# MCU.net
KiCad netlist of a schematic drawn in Altium Designer
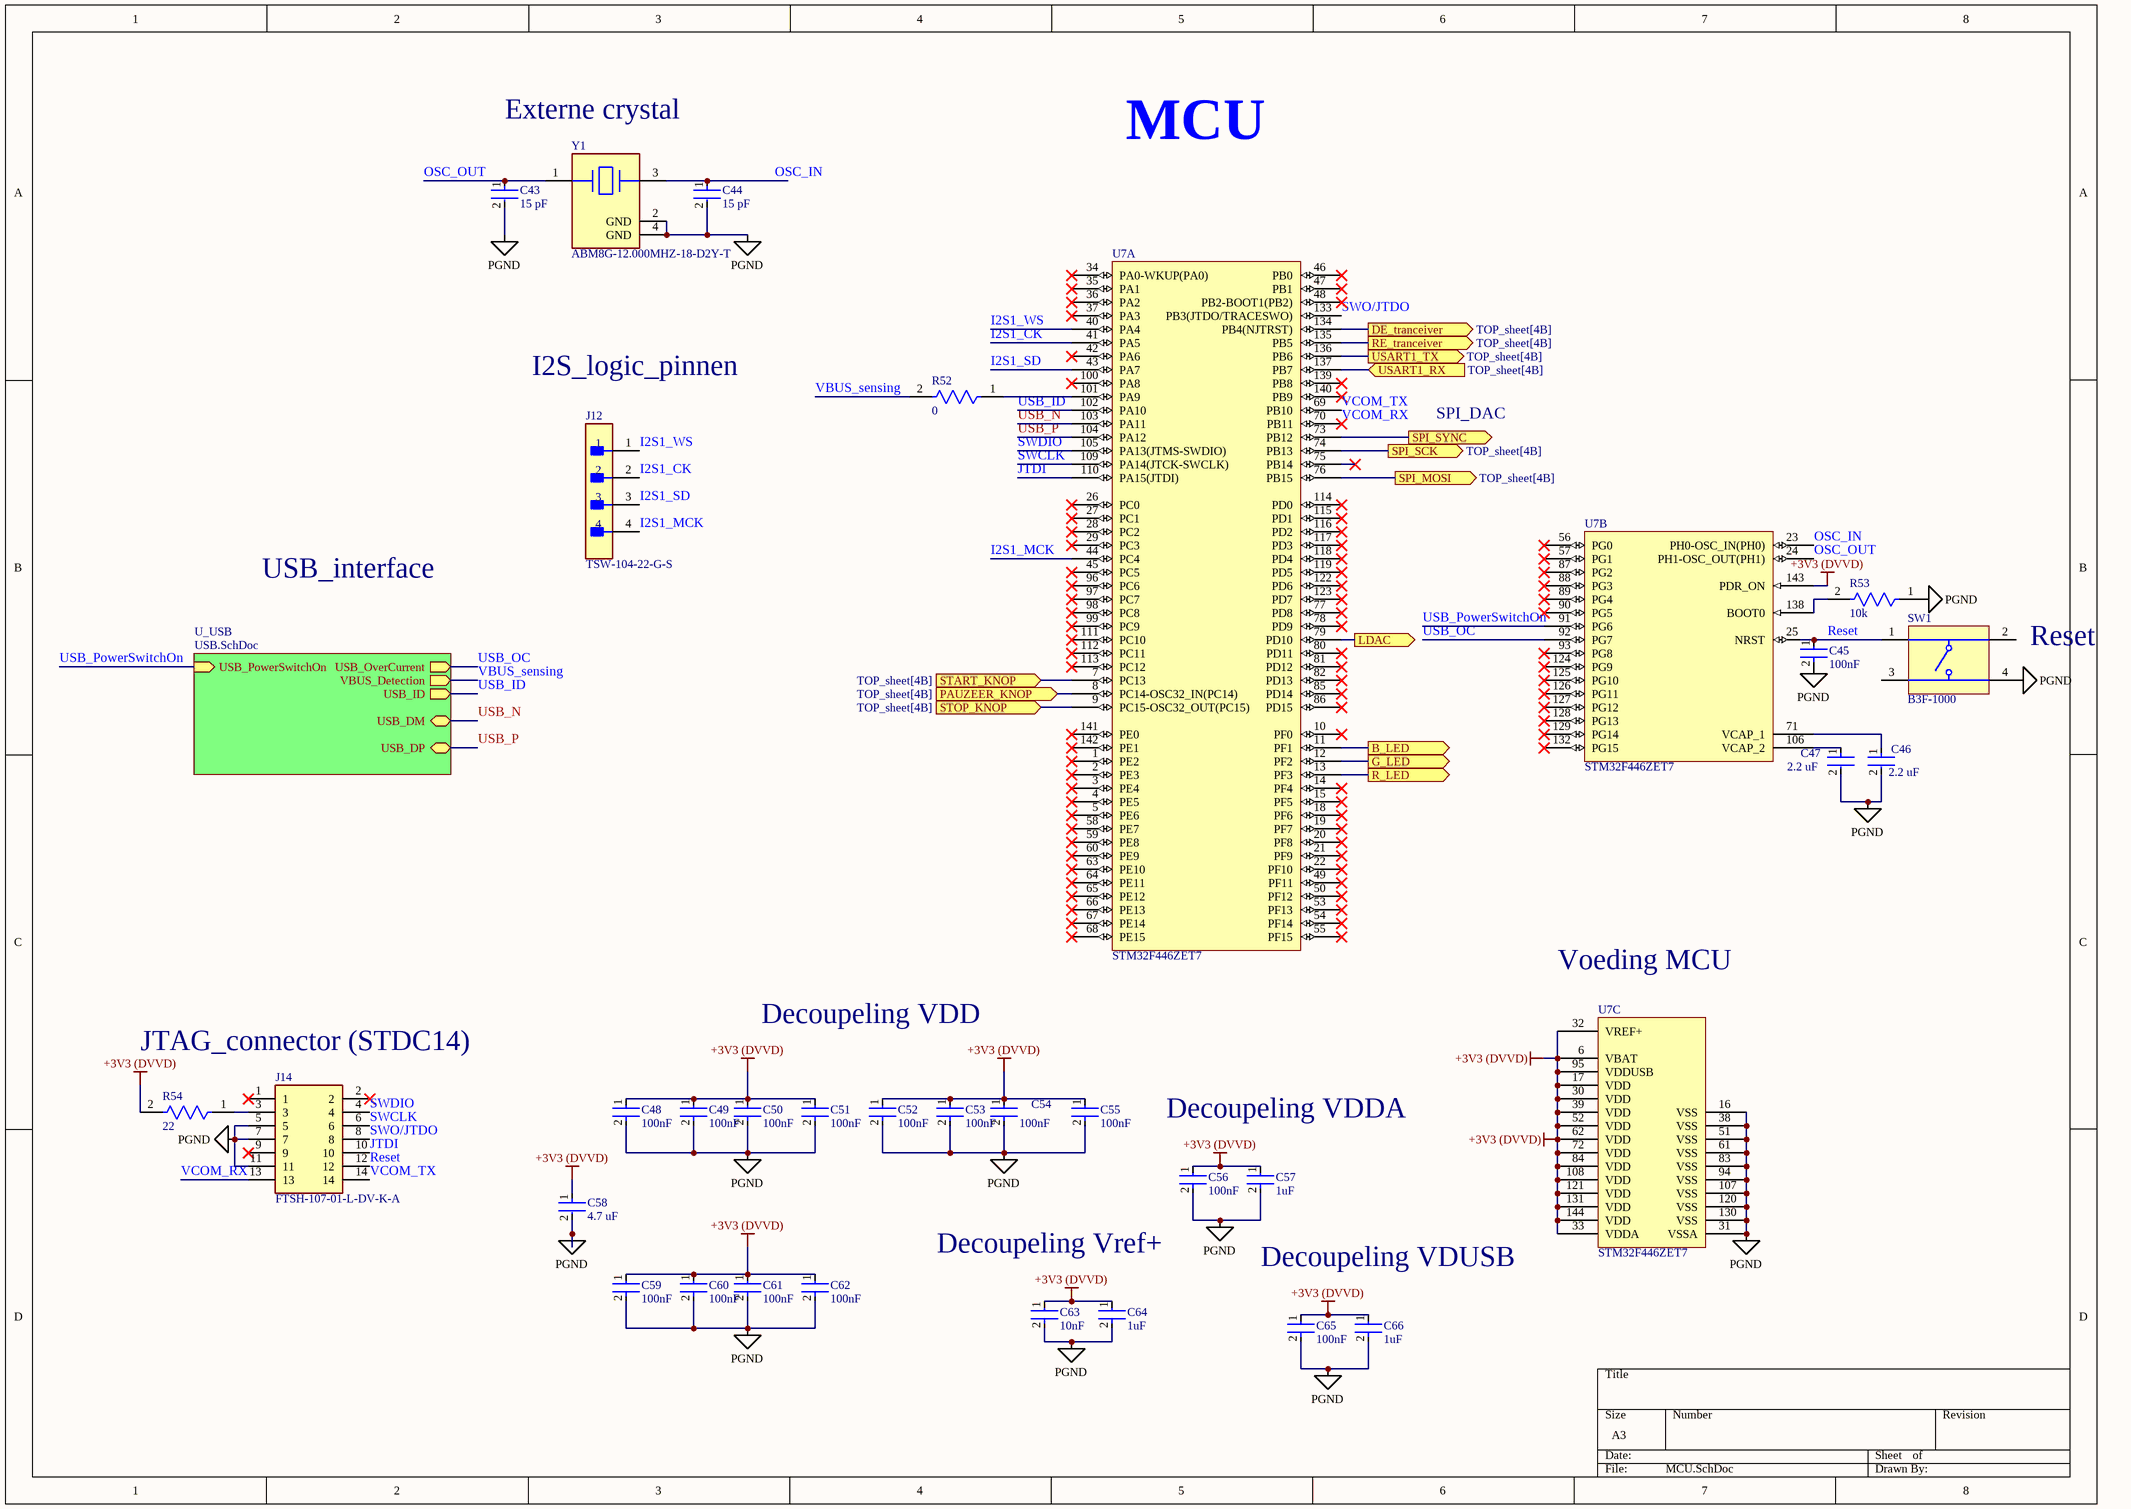
[diagram p0: MCU.SchDoc]

(export (version "E")
  (design (tool "Eeschema 10.0.6"))
  (components
    (comp (ref "C43")
      (value "15 pF")
      (footprint "FP-AC0603-MFG")
      (description "AC0603 15 pF NP0 5.00% 50 V")
      (fields
        (field (name "TOLERANCE") "0.05")
        (field (name "OCTOPART") "https://octopart.com/ac0603jrnpo9bn271-yageo-87214073")
      )
      (libsource (lib "Altium Content Vault") (part "11868f565c42a9108669ba33697ecf6"))
    )
    (comp (ref "C44")
      (value "15 pF")
      (footprint "FP-AC0603-MFG")
      (description "AC0603 15 pF NP0 5.00% 50 V")
      (fields
        (field (name "TOLERANCE") "0.05")
        (field (name "OCTOPART") "https://octopart.com/ac0603jrnpo9bn271-yageo-87214073")
      )
      (libsource (lib "Altium Content Vault") (part "11868f565c42a9108669ba33697ecf6"))
    )
    (comp (ref "C45")
      (value "100nF")
      (footprint "FP-GRM15-MFG")
      (description "CAP CER 0.1UF 16V X7R 0402")
      (fields (field (name "MANUFACTURER PART NUMBER") "GRM155R71C104KA88D") (field (name "TOLERANCE") "10%"))
      (libsource (lib "Altium Content Vault") (part "236180d848d6139a670b325ea6854c9"))
    )
    (comp (ref "C46")
      (value "2.2 uF")
      (footprint "FP-C0603C-CF-MFG")
      (description "CAP CER 2.2 UF 50V 5% X7R 0603")
      (fields (field (name "TOLERANCE") "0.05") (field (name "MANUFACTURER PART NUMBER") "C0603C104J5RACTU"))
      (libsource (lib "Altium Content Vault") (part "b4654b650e69147ec39a6b967a45e02"))
    )
    (comp (ref "C47")
      (value "2.2 uF")
      (footprint "FP-C0603C-CF-MFG")
      (description "CAP CER 2.2 UF 50V 5% X7R 0603")
      (fields (field (name "TOLERANCE") "0.05") (field (name "MANUFACTURER PART NUMBER") "C0603C104J5RACTU"))
      (libsource (lib "Altium Content Vault") (part "b4654b650e69147ec39a6b967a45e02"))
    )
    (comp (ref "C48")
      (value "100nF")
      (footprint "FP-GRM15-MFG")
      (description "CAP CER 0.1UF 16V X7R 0402")
      (fields (field (name "MANUFACTURER PART NUMBER") "GRM155R71C104KA88D") (field (name "TOLERANCE") "10%"))
      (libsource (lib "Altium Content Vault") (part "236180d848d6139a670b325ea6854c9"))
    )
    (comp (ref "C49")
      (value "100nF")
      (footprint "FP-GRM15-MFG")
      (description "CAP CER 0.1UF 16V X7R 0402")
      (fields (field (name "MANUFACTURER PART NUMBER") "GRM155R71C104KA88D") (field (name "TOLERANCE") "10%"))
      (libsource (lib "Altium Content Vault") (part "236180d848d6139a670b325ea6854c9"))
    )
    (comp (ref "C50")
      (value "100nF")
      (footprint "FP-GRM15-MFG")
      (description "CAP CER 0.1UF 16V X7R 0402")
      (fields (field (name "MANUFACTURER PART NUMBER") "GRM155R71C104KA88D") (field (name "TOLERANCE") "10%"))
      (libsource (lib "Altium Content Vault") (part "236180d848d6139a670b325ea6854c9"))
    )
    (comp (ref "C51")
      (value "100nF")
      (footprint "FP-GRM15-MFG")
      (description "CAP CER 0.1UF 16V X7R 0402")
      (fields (field (name "MANUFACTURER PART NUMBER") "GRM155R71C104KA88D") (field (name "TOLERANCE") "10%"))
      (libsource (lib "Altium Content Vault") (part "236180d848d6139a670b325ea6854c9"))
    )
    (comp (ref "C52")
      (value "100nF")
      (footprint "FP-GRM15-MFG")
      (description "CAP CER 0.1UF 16V X7R 0402")
      (fields (field (name "MANUFACTURER PART NUMBER") "GRM155R71C104KA88D") (field (name "TOLERANCE") "10%"))
      (libsource (lib "Altium Content Vault") (part "236180d848d6139a670b325ea6854c9"))
    )
    (comp (ref "C53")
      (value "100nF")
      (footprint "FP-GRM15-MFG")
      (description "CAP CER 0.1UF 16V X7R 0402")
      (fields (field (name "MANUFACTURER PART NUMBER") "GRM155R71C104KA88D") (field (name "TOLERANCE") "10%"))
      (libsource (lib "Altium Content Vault") (part "236180d848d6139a670b325ea6854c9"))
    )
    (comp (ref "C54")
      (value "100nF")
      (footprint "FP-GRM15-MFG")
      (description "CAP CER 0.1UF 16V X7R 0402")
      (fields (field (name "MANUFACTURER PART NUMBER") "GRM155R71C104KA88D") (field (name "TOLERANCE") "10%"))
      (libsource (lib "Altium Content Vault") (part "236180d848d6139a670b325ea6854c9"))
    )
    (comp (ref "C55")
      (value "100nF")
      (footprint "FP-GRM15-MFG")
      (description "CAP CER 0.1UF 16V X7R 0402")
      (fields (field (name "MANUFACTURER PART NUMBER") "GRM155R71C104KA88D") (field (name "TOLERANCE") "10%"))
      (libsource (lib "Altium Content Vault") (part "236180d848d6139a670b325ea6854c9"))
    )
    (comp (ref "C56")
      (value "100nF")
      (footprint "FP-GRM15-MFG")
      (description "CAP CER 0.1UF 16V X7R 0402")
      (fields (field (name "MANUFACTURER PART NUMBER") "GRM155R71C104KA88D") (field (name "TOLERANCE") "10%"))
      (libsource (lib "Altium Content Vault") (part "236180d848d6139a670b325ea6854c9"))
    )
    (comp (ref "C57")
      (value "1uF")
      (footprint "FP-GRM15-MFG")
      (description "CAP CER 1UF 16V X7R 0402")
      (fields (field (name "MANUFACTURER PART NUMBER") "GRM155R71C104KA88D") (field (name "TOLERANCE") "10%"))
      (libsource (lib "Altium Content Vault") (part "236180d848d6139a670b325ea6854c9"))
    )
    (comp (ref "C58")
      (value "4.7 uF")
      (footprint "FP-C0603C-CF-MFG")
      (description "CAP CER 4.7 UF 50V 5% X7R 0603")
      (fields (field (name "TOLERANCE") "0.05") (field (name "MANUFACTURER PART NUMBER") "C0603C104J5RACTU"))
      (libsource (lib "Altium Content Vault") (part "b4654b650e69147ec39a6b967a45e02"))
    )
    (comp (ref "C59")
      (value "100nF")
      (footprint "FP-GRM15-MFG")
      (description "CAP CER 0.1UF 16V X7R 0402")
      (fields (field (name "MANUFACTURER PART NUMBER") "GRM155R71C104KA88D") (field (name "TOLERANCE") "10%"))
      (libsource (lib "Altium Content Vault") (part "236180d848d6139a670b325ea6854c9"))
    )
    (comp (ref "C60")
      (value "100nF")
      (footprint "FP-GRM15-MFG")
      (description "CAP CER 0.1UF 16V X7R 0402")
      (fields (field (name "MANUFACTURER PART NUMBER") "GRM155R71C104KA88D") (field (name "TOLERANCE") "10%"))
      (libsource (lib "Altium Content Vault") (part "236180d848d6139a670b325ea6854c9"))
    )
    (comp (ref "C61")
      (value "100nF")
      (footprint "FP-GRM15-MFG")
      (description "CAP CER 0.1UF 16V X7R 0402")
      (fields (field (name "MANUFACTURER PART NUMBER") "GRM155R71C104KA88D") (field (name "TOLERANCE") "10%"))
      (libsource (lib "Altium Content Vault") (part "236180d848d6139a670b325ea6854c9"))
    )
    (comp (ref "C62")
      (value "100nF")
      (footprint "FP-GRM15-MFG")
      (description "CAP CER 0.1UF 16V X7R 0402")
      (fields (field (name "MANUFACTURER PART NUMBER") "GRM155R71C104KA88D") (field (name "TOLERANCE") "10%"))
      (libsource (lib "Altium Content Vault") (part "236180d848d6139a670b325ea6854c9"))
    )
    (comp (ref "C63")
      (value "10nF")
      (footprint "FP-GRM15-MFG")
      (description "CAP CER 10nF 16V X7R 0402")
      (fields (field (name "MANUFACTURER PART NUMBER") "GRM155R71C104KA88D") (field (name "TOLERANCE") "10%"))
      (libsource (lib "Altium Content Vault") (part "236180d848d6139a670b325ea6854c9"))
    )
    (comp (ref "C64")
      (value "1uF")
      (footprint "FP-GRM15-MFG")
      (description "CAP CER 1UF 16V X7R 0402")
      (fields (field (name "MANUFACTURER PART NUMBER") "GRM155R71C104KA88D") (field (name "TOLERANCE") "10%"))
      (libsource (lib "Altium Content Vault") (part "236180d848d6139a670b325ea6854c9"))
    )
    (comp (ref "C65")
      (value "100nF")
      (footprint "FP-GRM15-MFG")
      (description "CAP CER 0.1UF 16V X7R 0402")
      (fields (field (name "MANUFACTURER PART NUMBER") "GRM155R71C104KA88D") (field (name "TOLERANCE") "10%"))
      (libsource (lib "Altium Content Vault") (part "236180d848d6139a670b325ea6854c9"))
    )
    (comp (ref "C66")
      (value "1uF")
      (footprint "FP-GRM15-MFG")
      (description "CAP CER 1UF 16V X7R 0402")
      (fields (field (name "MANUFACTURER PART NUMBER") "GRM155R71C104KA88D") (field (name "TOLERANCE") "10%"))
      (libsource (lib "Altium Content Vault") (part "236180d848d6139a670b325ea6854c9"))
    )
    (comp (ref "J12")
      (value "TSW-104-22-G-S")
      (footprint "FP-TSW-104-22-G-S-MFG")
      (description "GENERIC PART NUMBER: GPHA-1X04\r\nCONN HEADER VERT 4POS 2.54MM")
      (fields (field (name "GENERIC PART NUMBER") "GPHA-1X04"))
      (libsource (lib "Altium Content Vault") (part "299a8cea1bdcbc3624fe62c390fa72c"))
    )
    (comp (ref "J14")
      (value "FTSH-107-01-L-DV-K-A")
      (footprint "SamacSys:FTSH-107-XX-YYY-DV-K-A")
      (fields (field (name "MOUSER PART NUMBER") "200-FTSH10701LDVKA"))
      (libsource (lib "*") (part "FTSH-107-01-L-DV-K-A"))
    )
    (comp (ref "R52")
      (value "0")
      (footprint "FP-CRCW1206-MFG")
      (description "CRCW12060000ZSTA Zero Ohm Resistor, Jumper, 1206 [3216 Metric], Thick Film, 250 mW, Surface Mount")
      (libsource (lib "Altium Content Vault") (part "1029c3af85768c4190bb7ad29bc67b5"))
    )
    (comp (ref "R53")
      (value "10k")
      (footprint "FP-RC1608-IPC_B")
      (fields (field (name "TOLERANCE") "1%"))
      (libsource (lib "Altium Content Vault") (part "1029c3af85768c4190bb7ad29bc67b5"))
    )
    (comp (ref "R54")
      (value "22")
      (footprint "FP-RC1608-IPC_B")
      (fields (field (name "TOLERANCE") "1%"))
      (libsource (lib "Altium Content Vault") (part "1029c3af85768c4190bb7ad29bc67b5"))
    )
    (comp (ref "SW1")
      (value "B3F-1000")
      (footprint "OMRON-B3F-1000-4_V")
      (description "Tactile Switch, SPST-NO, 0.05 A, 5 to 24 V, -25 to 70 degC, 4-Pin THD, RoHS, Bulk")
      (libsource (lib "Altium Content Vault") (part "SW-SPST-4_A"))
    )
    (comp (ref "U7")
      (value "STM32F446ZET7")
      (footprint "STM-LQFP144_M")
      (libsource (lib "Altium Content Vault") (part "MC-ARM-STM32F446-LQFP144"))
    )
    (comp (ref "Y1")
      (value "ABM8G-12.000MHZ-18-D2Y-T")
      (footprint "FP-ABM8G-MFG")
      (description "Crystal 12MHz ±20ppm (Tol) ±30ppm (Stability) 18pF FUND 120Ω 4-Pin SMD T/R")
      (fields (field (name "TOLERANCE") "20ppm"))
      (libsource (lib "Altium Content Vault") (part "48e526d86b7f2615d98721063c72f49"))
    )
  )
  (nets
    (net (code "1") (name "+3V3 (DVVD)") (class "Default")
      (node (ref "C48") (pin "1") (pinfunction "1_1") (pintype "passive"))
      (node (ref "C49") (pin "1") (pinfunction "1_1") (pintype "passive"))
      (node (ref "C50") (pin "1") (pinfunction "1_1") (pintype "passive"))
      (node (ref "C51") (pin "1") (pinfunction "1_1") (pintype "passive"))
      (node (ref "C52") (pin "1") (pinfunction "1_1") (pintype "passive"))
      (node (ref "C53") (pin "1") (pinfunction "1_1") (pintype "passive"))
      (node (ref "C54") (pin "1") (pinfunction "1_1") (pintype "passive"))
      (node (ref "C55") (pin "1") (pinfunction "1_1") (pintype "passive"))
      (node (ref "C56") (pin "1") (pinfunction "1_1") (pintype "passive"))
      (node (ref "C57") (pin "1") (pinfunction "1_1") (pintype "passive"))
      (node (ref "C58") (pin "1") (pinfunction "1_1") (pintype "passive"))
      (node (ref "C59") (pin "1") (pinfunction "1_1") (pintype "passive"))
      (node (ref "C60") (pin "1") (pinfunction "1_1") (pintype "passive"))
      (node (ref "C61") (pin "1") (pinfunction "1_1") (pintype "passive"))
      (node (ref "C62") (pin "1") (pinfunction "1_1") (pintype "passive"))
      (node (ref "C63") (pin "1") (pinfunction "1_1") (pintype "passive"))
      (node (ref "C64") (pin "1") (pinfunction "1_1") (pintype "passive"))
      (node (ref "C65") (pin "1") (pinfunction "1_1") (pintype "passive"))
      (node (ref "C66") (pin "1") (pinfunction "1_1") (pintype "passive"))
      (node (ref "R54") (pin "2") (pinfunction "2_2") (pintype "passive"))
      (node (ref "U7") (pin "108") (pinfunction "VDD_108") (pintype "power_in"))
      (node (ref "U7") (pin "121") (pinfunction "VDD_121") (pintype "power_in"))
      (node (ref "U7") (pin "131") (pinfunction "VDD_131") (pintype "power_in"))
      (node (ref "U7") (pin "143") (pinfunction "PDR_ON_143") (pintype "input"))
      (node (ref "U7") (pin "144") (pinfunction "VDD_144") (pintype "power_in"))
      (node (ref "U7") (pin "17") (pinfunction "VDD_17") (pintype "power_in"))
      (node (ref "U7") (pin "30") (pinfunction "VDD_30") (pintype "power_in"))
      (node (ref "U7") (pin "32") (pinfunction "VREF+_32") (pintype "power_in"))
      (node (ref "U7") (pin "33") (pinfunction "VDDA_33") (pintype "power_in"))
      (node (ref "U7") (pin "39") (pinfunction "VDD_39") (pintype "power_in"))
      (node (ref "U7") (pin "52") (pinfunction "VDD_52") (pintype "power_in"))
      (node (ref "U7") (pin "6") (pinfunction "VBAT_6") (pintype "power_in"))
      (node (ref "U7") (pin "62") (pinfunction "VDD_62") (pintype "power_in"))
      (node (ref "U7") (pin "72") (pinfunction "VDD_72") (pintype "power_in"))
      (node (ref "U7") (pin "84") (pinfunction "VDD_84") (pintype "power_in"))
      (node (ref "U7") (pin "95") (pinfunction "VDDUSB_95") (pintype "power_in"))
    )
    (net (code "3") (name "/B_LED") (class "Default")
      (node (ref "U7") (pin "11") (pinfunction "PF1_11") (pintype "bidirectional"))
    )
    (net (code "4") (name "/DE_tranceiver") (class "Default")
      (node (ref "U7") (pin "134") (pinfunction "PB4(NJTRST)_134") (pintype "bidirectional"))
    )
    (net (code "5") (name "/G_LED") (class "Default")
      (node (ref "U7") (pin "12") (pinfunction "PF2_12") (pintype "bidirectional"))
    )
    (net (code "6") (name "/I2S1_CK") (class "Default")
      (node (ref "J12") (pin "2") (pinfunction "2_2") (pintype "passive"))
      (node (ref "U7") (pin "41") (pinfunction "PA5_41") (pintype "bidirectional"))
    )
    (net (code "7") (name "/I2S1_MCK") (class "Default")
      (node (ref "J12") (pin "4") (pinfunction "4_4") (pintype "passive"))
      (node (ref "U7") (pin "44") (pinfunction "PC4_44") (pintype "bidirectional"))
    )
    (net (code "8") (name "/I2S1_SD") (class "Default")
      (node (ref "J12") (pin "3") (pinfunction "3_3") (pintype "passive"))
      (node (ref "U7") (pin "43") (pinfunction "PA7_43") (pintype "bidirectional"))
    )
    (net (code "9") (name "/I2S1_WS") (class "Default")
      (node (ref "J12") (pin "1") (pinfunction "1_1") (pintype "passive"))
      (node (ref "U7") (pin "40") (pinfunction "PA4_40") (pintype "bidirectional"))
    )
    (net (code "10") (name "/JTDI") (class "Default")
      (node (ref "J14") (pin "10") (pinfunction "10_10") (pintype "passive"))
      (node (ref "U7") (pin "110") (pinfunction "PA15(JTDI)_110") (pintype "bidirectional"))
    )
    (net (code "11") (name "/LDAC") (class "Default")
      (node (ref "U7") (pin "79") (pinfunction "PD10_79") (pintype "bidirectional"))
    )
    (net (code "12") (name "/OSC_IN") (class "Default")
      (node (ref "C44") (pin "1") (pinfunction "1_1") (pintype "passive"))
      (node (ref "U7") (pin "23") (pinfunction "PH0-OSC_IN(PH0)_23") (pintype "bidirectional"))
      (node (ref "Y1") (pin "3") (pinfunction "3_3") (pintype "passive"))
    )
    (net (code "13") (name "/OSC_OUT") (class "Default")
      (node (ref "C43") (pin "1") (pinfunction "1_1") (pintype "passive"))
      (node (ref "U7") (pin "24") (pinfunction "PH1-OSC_OUT(PH1)_24") (pintype "bidirectional"))
      (node (ref "Y1") (pin "1") (pinfunction "1_1") (pintype "passive"))
    )
    (net (code "14") (name "/PAUZEER_KNOP") (class "Default")
      (node (ref "U7") (pin "8") (pinfunction "PC14-OSC32_IN(PC14)_8") (pintype "bidirectional"))
    )
    (net (code "15") (name "/RE_tranceiver") (class "Default")
      (node (ref "U7") (pin "135") (pinfunction "PB5_135") (pintype "bidirectional"))
    )
    (net (code "16") (name "/R_LED") (class "Default")
      (node (ref "U7") (pin "13") (pinfunction "PF3_13") (pintype "bidirectional"))
    )
    (net (code "17") (name "/Reset") (class "Default")
      (node (ref "C45") (pin "1") (pinfunction "1_1") (pintype "passive"))
      (node (ref "J14") (pin "12") (pinfunction "12_12") (pintype "passive"))
      (node (ref "SW1") (pin "1") (pinfunction "1_1") (pintype "passive"))
      (node (ref "U7") (pin "25") (pinfunction "NRST_25") (pintype "bidirectional"))
    )
    (net (code "18") (name "/SPI_MOSI") (class "Default")
      (node (ref "U7") (pin "76") (pinfunction "PB15_76") (pintype "bidirectional"))
    )
    (net (code "19") (name "/SPI_SCK") (class "Default")
      (node (ref "U7") (pin "74") (pinfunction "PB13_74") (pintype "bidirectional"))
    )
    (net (code "20") (name "/SPI_SYNC") (class "Default")
      (node (ref "U7") (pin "73") (pinfunction "PB12_73") (pintype "bidirectional"))
    )
    (net (code "21") (name "/START_KNOP") (class "Default")
      (node (ref "U7") (pin "7") (pinfunction "PC13_7") (pintype "bidirectional"))
    )
    (net (code "22") (name "/STOP_KNOP") (class "Default")
      (node (ref "U7") (pin "9") (pinfunction "PC15-OSC32_OUT(PC15)_9") (pintype "bidirectional"))
    )
    (net (code "23") (name "/SWCLK") (class "Default")
      (node (ref "J14") (pin "6") (pinfunction "6_6") (pintype "passive"))
      (node (ref "U7") (pin "109") (pinfunction "PA14(JTCK-SWCLK)_109") (pintype "bidirectional"))
    )
    (net (code "24") (name "/SWDIO") (class "Default")
      (node (ref "J14") (pin "4") (pinfunction "4_4") (pintype "passive"))
      (node (ref "U7") (pin "105") (pinfunction "PA13(JTMS-SWDIO)_105") (pintype "bidirectional"))
    )
    (net (code "25") (name "/SWO{slash}JTDO") (class "Default")
      (node (ref "J14") (pin "8") (pinfunction "8_8") (pintype "passive"))
      (node (ref "U7") (pin "133") (pinfunction "PB3(JTDO/TRACESWO)_133") (pintype "bidirectional"))
    )
    (net (code "26") (name "/USART1_RX") (class "Default")
      (node (ref "U7") (pin "137") (pinfunction "PB7_137") (pintype "bidirectional"))
    )
    (net (code "27") (name "/USART1_TX") (class "Default")
      (node (ref "U7") (pin "136") (pinfunction "PB6_136") (pintype "bidirectional"))
    )
    (net (code "28") (name "/USB_ID") (class "Default")
      (node (ref "U7") (pin "102") (pinfunction "PA10_102") (pintype "bidirectional"))
    )
    (net (code "29") (name "/USB_N") (class "Default")
      (node (ref "U7") (pin "103") (pinfunction "PA11_103") (pintype "bidirectional"))
    )
    (net (code "30") (name "/USB_OC") (class "Default")
      (node (ref "U7") (pin "92") (pinfunction "PG7_92") (pintype "bidirectional"))
    )
    (net (code "31") (name "/USB_P") (class "Default")
      (node (ref "U7") (pin "104") (pinfunction "PA12_104") (pintype "bidirectional"))
    )
    (net (code "32") (name "/USB_PowerSwitchOn") (class "Default")
      (node (ref "U7") (pin "91") (pinfunction "PG6_91") (pintype "bidirectional"))
    )
    (net (code "33") (name "/VBUS_sensing") (class "Default")
      (node (ref "R52") (pin "2") (pinfunction "2_2") (pintype "passive"))
    )
    (net (code "34") (name "/VCOM_RX") (class "Default")
      (node (ref "J14") (pin "13") (pinfunction "13_13") (pintype "passive"))
      (node (ref "U7") (pin "70") (pinfunction "PB11_70") (pintype "bidirectional"))
    )
    (net (code "35") (name "/VCOM_TX") (class "Default")
      (node (ref "J14") (pin "14") (pinfunction "14_14") (pintype "passive"))
      (node (ref "U7") (pin "69") (pinfunction "PB10_69") (pintype "bidirectional"))
    )
    (net (code "36") (name "Net-(J14-Pad3)") (class "Default")
      (node (ref "J14") (pin "3") (pinfunction "3_3") (pintype "passive"))
      (node (ref "R54") (pin "1") (pinfunction "1_1") (pintype "passive"))
    )
    (net (code "37") (name "Net-(U7A-PA9)") (class "Default")
      (node (ref "R52") (pin "1") (pinfunction "1_1") (pintype "passive"))
      (node (ref "U7") (pin "101") (pinfunction "PA9_101") (pintype "bidirectional"))
    )
    (net (code "38") (name "Net-(U7B-BOOT0)") (class "Default")
      (node (ref "R53") (pin "2") (pinfunction "2_2") (pintype "passive"))
      (node (ref "U7") (pin "138") (pinfunction "BOOT0_138") (pintype "input"))
    )
    (net (code "39") (name "Net-(U7B-VCAP_1)") (class "Default")
      (node (ref "C46") (pin "1") (pinfunction "1_1") (pintype "passive"))
      (node (ref "U7") (pin "71") (pinfunction "VCAP_1_71") (pintype "passive"))
    )
    (net (code "40") (name "Net-(U7B-VCAP_2)") (class "Default")
      (node (ref "C47") (pin "1") (pinfunction "1_1") (pintype "passive"))
      (node (ref "U7") (pin "106") (pinfunction "VCAP_2_106") (pintype "passive"))
    )
    (net (code "41") (name "PGND") (class "Default")
      (node (ref "C43") (pin "2") (pinfunction "2_2") (pintype "passive"))
      (node (ref "C44") (pin "2") (pinfunction "2_2") (pintype "passive"))
      (node (ref "C45") (pin "2") (pinfunction "2_2") (pintype "passive"))
      (node (ref "C46") (pin "2") (pinfunction "2_2") (pintype "passive"))
      (node (ref "C47") (pin "2") (pinfunction "2_2") (pintype "passive"))
      (node (ref "C48") (pin "2") (pinfunction "2_2") (pintype "passive"))
      (node (ref "C49") (pin "2") (pinfunction "2_2") (pintype "passive"))
      (node (ref "C50") (pin "2") (pinfunction "2_2") (pintype "passive"))
      (node (ref "C51") (pin "2") (pinfunction "2_2") (pintype "passive"))
      (node (ref "C52") (pin "2") (pinfunction "2_2") (pintype "passive"))
      (node (ref "C53") (pin "2") (pinfunction "2_2") (pintype "passive"))
      (node (ref "C54") (pin "2") (pinfunction "2_2") (pintype "passive"))
      (node (ref "C55") (pin "2") (pinfunction "2_2") (pintype "passive"))
      (node (ref "C56") (pin "2") (pinfunction "2_2") (pintype "passive"))
      (node (ref "C57") (pin "2") (pinfunction "2_2") (pintype "passive"))
      (node (ref "C58") (pin "2") (pinfunction "2_2") (pintype "passive"))
      (node (ref "C59") (pin "2") (pinfunction "2_2") (pintype "passive"))
      (node (ref "C60") (pin "2") (pinfunction "2_2") (pintype "passive"))
      (node (ref "C61") (pin "2") (pinfunction "2_2") (pintype "passive"))
      (node (ref "C62") (pin "2") (pinfunction "2_2") (pintype "passive"))
      (node (ref "C63") (pin "2") (pinfunction "2_2") (pintype "passive"))
      (node (ref "C64") (pin "2") (pinfunction "2_2") (pintype "passive"))
      (node (ref "C65") (pin "2") (pinfunction "2_2") (pintype "passive"))
      (node (ref "C66") (pin "2") (pinfunction "2_2") (pintype "passive"))
      (node (ref "J14") (pin "11") (pinfunction "11_11") (pintype "passive"))
      (node (ref "J14") (pin "5") (pinfunction "5_5") (pintype "passive"))
      (node (ref "J14") (pin "7") (pinfunction "7_7") (pintype "passive"))
      (node (ref "R53") (pin "1") (pinfunction "1_1") (pintype "passive"))
      (node (ref "SW1") (pin "4") (pinfunction "4_4") (pintype "passive"))
      (node (ref "U7") (pin "107") (pinfunction "VSS_107") (pintype "power_in"))
      (node (ref "U7") (pin "120") (pinfunction "VSS_120") (pintype "power_in"))
      (node (ref "U7") (pin "130") (pinfunction "VSS_130") (pintype "power_in"))
      (node (ref "U7") (pin "16") (pinfunction "VSS_16") (pintype "power_in"))
      (node (ref "U7") (pin "31") (pinfunction "VSSA_31") (pintype "power_in"))
      (node (ref "U7") (pin "38") (pinfunction "VSS_38") (pintype "power_in"))
      (node (ref "U7") (pin "51") (pinfunction "VSS_51") (pintype "power_in"))
      (node (ref "U7") (pin "61") (pinfunction "VSS_61") (pintype "power_in"))
      (node (ref "U7") (pin "83") (pinfunction "VSS_83") (pintype "power_in"))
      (node (ref "U7") (pin "94") (pinfunction "VSS_94") (pintype "power_in"))
      (node (ref "Y1") (pin "2") (pinfunction "GND_2") (pintype "power_in"))
      (node (ref "Y1") (pin "4") (pinfunction "GND_4") (pintype "power_in"))
    )
    (net (code "42") (name "unconnected-(J14-Pad1)") (class "Default")
      (node (ref "J14") (pin "1") (pinfunction "1_1") (pintype "passive+no_connect"))
    )
    (net (code "43") (name "unconnected-(J14-Pad2)") (class "Default")
      (node (ref "J14") (pin "2") (pinfunction "2_2") (pintype "passive+no_connect"))
    )
    (net (code "44") (name "unconnected-(J14-Pad9)") (class "Default")
      (node (ref "J14") (pin "9") (pinfunction "9_9") (pintype "passive+no_connect"))
    )
    (net (code "45") (name "unconnected-(SW1-Pad2)") (class "Default")
      (node (ref "SW1") (pin "2") (pinfunction "2_2") (pintype "passive"))
    )
    (net (code "46") (name "unconnected-(SW1-Pad3)") (class "Default")
      (node (ref "SW1") (pin "3") (pinfunction "3_3") (pintype "passive"))
    )
    (net (code "47") (name "unconnected-(U7A-PA0-WKUP(PA0)-Pad34)") (class "Default")
      (node (ref "U7") (pin "34") (pinfunction "PA0-WKUP(PA0)_34") (pintype "bidirectional+no_connect"))
    )
    (net (code "48") (name "unconnected-(U7A-PA1-Pad35)") (class "Default")
      (node (ref "U7") (pin "35") (pinfunction "PA1_35") (pintype "bidirectional+no_connect"))
    )
    (net (code "49") (name "unconnected-(U7A-PA2-Pad36)") (class "Default")
      (node (ref "U7") (pin "36") (pinfunction "PA2_36") (pintype "bidirectional+no_connect"))
    )
    (net (code "50") (name "unconnected-(U7A-PA3-Pad37)") (class "Default")
      (node (ref "U7") (pin "37") (pinfunction "PA3_37") (pintype "bidirectional+no_connect"))
    )
    (net (code "51") (name "unconnected-(U7A-PA6-Pad42)") (class "Default")
      (node (ref "U7") (pin "42") (pinfunction "PA6_42") (pintype "bidirectional+no_connect"))
    )
    (net (code "52") (name "unconnected-(U7A-PA8-Pad100)") (class "Default")
      (node (ref "U7") (pin "100") (pinfunction "PA8_100") (pintype "bidirectional+no_connect"))
    )
    (net (code "53") (name "unconnected-(U7A-PB0-Pad46)") (class "Default")
      (node (ref "U7") (pin "46") (pinfunction "PB0_46") (pintype "bidirectional+no_connect"))
    )
    (net (code "54") (name "unconnected-(U7A-PB1-Pad47)") (class "Default")
      (node (ref "U7") (pin "47") (pinfunction "PB1_47") (pintype "bidirectional+no_connect"))
    )
    (net (code "55") (name "unconnected-(U7A-PB2-BOOT1(PB2)-Pad48)") (class "Default")
      (node (ref "U7") (pin "48") (pinfunction "PB2-BOOT1(PB2)_48") (pintype "bidirectional+no_connect"))
    )
    (net (code "56") (name "unconnected-(U7A-PB8-Pad139)") (class "Default")
      (node (ref "U7") (pin "139") (pinfunction "PB8_139") (pintype "bidirectional+no_connect"))
    )
    (net (code "57") (name "unconnected-(U7A-PB9-Pad140)") (class "Default")
      (node (ref "U7") (pin "140") (pinfunction "PB9_140") (pintype "bidirectional+no_connect"))
    )
    (net (code "58") (name "unconnected-(U7A-PB14-Pad75)") (class "Default")
      (node (ref "U7") (pin "75") (pinfunction "PB14_75") (pintype "bidirectional+no_connect"))
    )
    (net (code "59") (name "unconnected-(U7A-PC0-Pad26)") (class "Default")
      (node (ref "U7") (pin "26") (pinfunction "PC0_26") (pintype "bidirectional+no_connect"))
    )
    (net (code "60") (name "unconnected-(U7A-PC1-Pad27)") (class "Default")
      (node (ref "U7") (pin "27") (pinfunction "PC1_27") (pintype "bidirectional+no_connect"))
    )
    (net (code "61") (name "unconnected-(U7A-PC2-Pad28)") (class "Default")
      (node (ref "U7") (pin "28") (pinfunction "PC2_28") (pintype "bidirectional+no_connect"))
    )
    (net (code "62") (name "unconnected-(U7A-PC3-Pad29)") (class "Default")
      (node (ref "U7") (pin "29") (pinfunction "PC3_29") (pintype "bidirectional+no_connect"))
    )
    (net (code "63") (name "unconnected-(U7A-PC5-Pad45)") (class "Default")
      (node (ref "U7") (pin "45") (pinfunction "PC5_45") (pintype "bidirectional+no_connect"))
    )
    (net (code "64") (name "unconnected-(U7A-PC6-Pad96)") (class "Default")
      (node (ref "U7") (pin "96") (pinfunction "PC6_96") (pintype "bidirectional+no_connect"))
    )
    (net (code "65") (name "unconnected-(U7A-PC7-Pad97)") (class "Default")
      (node (ref "U7") (pin "97") (pinfunction "PC7_97") (pintype "bidirectional+no_connect"))
    )
    (net (code "66") (name "unconnected-(U7A-PC8-Pad98)") (class "Default")
      (node (ref "U7") (pin "98") (pinfunction "PC8_98") (pintype "bidirectional+no_connect"))
    )
    (net (code "67") (name "unconnected-(U7A-PC9-Pad99)") (class "Default")
      (node (ref "U7") (pin "99") (pinfunction "PC9_99") (pintype "bidirectional+no_connect"))
    )
    (net (code "68") (name "unconnected-(U7A-PC10-Pad111)") (class "Default")
      (node (ref "U7") (pin "111") (pinfunction "PC10_111") (pintype "bidirectional+no_connect"))
    )
    (net (code "69") (name "unconnected-(U7A-PC11-Pad112)") (class "Default")
      (node (ref "U7") (pin "112") (pinfunction "PC11_112") (pintype "bidirectional+no_connect"))
    )
    (net (code "70") (name "unconnected-(U7A-PC12-Pad113)") (class "Default")
      (node (ref "U7") (pin "113") (pinfunction "PC12_113") (pintype "bidirectional+no_connect"))
    )
    (net (code "71") (name "unconnected-(U7A-PD0-Pad114)") (class "Default")
      (node (ref "U7") (pin "114") (pinfunction "PD0_114") (pintype "bidirectional+no_connect"))
    )
    (net (code "72") (name "unconnected-(U7A-PD1-Pad115)") (class "Default")
      (node (ref "U7") (pin "115") (pinfunction "PD1_115") (pintype "bidirectional+no_connect"))
    )
    (net (code "73") (name "unconnected-(U7A-PD2-Pad116)") (class "Default")
      (node (ref "U7") (pin "116") (pinfunction "PD2_116") (pintype "bidirectional+no_connect"))
    )
    (net (code "74") (name "unconnected-(U7A-PD3-Pad117)") (class "Default")
      (node (ref "U7") (pin "117") (pinfunction "PD3_117") (pintype "bidirectional+no_connect"))
    )
    (net (code "75") (name "unconnected-(U7A-PD4-Pad118)") (class "Default")
      (node (ref "U7") (pin "118") (pinfunction "PD4_118") (pintype "bidirectional+no_connect"))
    )
    (net (code "76") (name "unconnected-(U7A-PD5-Pad119)") (class "Default")
      (node (ref "U7") (pin "119") (pinfunction "PD5_119") (pintype "bidirectional+no_connect"))
    )
    (net (code "77") (name "unconnected-(U7A-PD6-Pad122)") (class "Default")
      (node (ref "U7") (pin "122") (pinfunction "PD6_122") (pintype "bidirectional+no_connect"))
    )
    (net (code "78") (name "unconnected-(U7A-PD7-Pad123)") (class "Default")
      (node (ref "U7") (pin "123") (pinfunction "PD7_123") (pintype "bidirectional+no_connect"))
    )
    (net (code "79") (name "unconnected-(U7A-PD8-Pad77)") (class "Default")
      (node (ref "U7") (pin "77") (pinfunction "PD8_77") (pintype "bidirectional+no_connect"))
    )
    (net (code "80") (name "unconnected-(U7A-PD9-Pad78)") (class "Default")
      (node (ref "U7") (pin "78") (pinfunction "PD9_78") (pintype "bidirectional+no_connect"))
    )
    (net (code "81") (name "unconnected-(U7A-PD11-Pad80)") (class "Default")
      (node (ref "U7") (pin "80") (pinfunction "PD11_80") (pintype "bidirectional+no_connect"))
    )
    (net (code "82") (name "unconnected-(U7A-PD12-Pad81)") (class "Default")
      (node (ref "U7") (pin "81") (pinfunction "PD12_81") (pintype "bidirectional+no_connect"))
    )
    (net (code "83") (name "unconnected-(U7A-PD13-Pad82)") (class "Default")
      (node (ref "U7") (pin "82") (pinfunction "PD13_82") (pintype "bidirectional+no_connect"))
    )
    (net (code "84") (name "unconnected-(U7A-PD14-Pad85)") (class "Default")
      (node (ref "U7") (pin "85") (pinfunction "PD14_85") (pintype "bidirectional+no_connect"))
    )
    (net (code "85") (name "unconnected-(U7A-PD15-Pad86)") (class "Default")
      (node (ref "U7") (pin "86") (pinfunction "PD15_86") (pintype "bidirectional+no_connect"))
    )
    (net (code "86") (name "unconnected-(U7A-PE0-Pad141)") (class "Default")
      (node (ref "U7") (pin "141") (pinfunction "PE0_141") (pintype "bidirectional+no_connect"))
    )
    (net (code "87") (name "unconnected-(U7A-PE1-Pad142)") (class "Default")
      (node (ref "U7") (pin "142") (pinfunction "PE1_142") (pintype "bidirectional+no_connect"))
    )
    (net (code "88") (name "unconnected-(U7A-PE2-Pad1)") (class "Default")
      (node (ref "U7") (pin "1") (pinfunction "PE2_1") (pintype "bidirectional+no_connect"))
    )
    (net (code "89") (name "unconnected-(U7A-PE3-Pad2)") (class "Default")
      (node (ref "U7") (pin "2") (pinfunction "PE3_2") (pintype "bidirectional+no_connect"))
    )
    (net (code "90") (name "unconnected-(U7A-PE4-Pad3)") (class "Default")
      (node (ref "U7") (pin "3") (pinfunction "PE4_3") (pintype "bidirectional+no_connect"))
    )
    (net (code "91") (name "unconnected-(U7A-PE5-Pad4)") (class "Default")
      (node (ref "U7") (pin "4") (pinfunction "PE5_4") (pintype "bidirectional+no_connect"))
    )
    (net (code "92") (name "unconnected-(U7A-PE6-Pad5)") (class "Default")
      (node (ref "U7") (pin "5") (pinfunction "PE6_5") (pintype "bidirectional+no_connect"))
    )
    (net (code "93") (name "unconnected-(U7A-PE7-Pad58)") (class "Default")
      (node (ref "U7") (pin "58") (pinfunction "PE7_58") (pintype "bidirectional+no_connect"))
    )
    (net (code "94") (name "unconnected-(U7A-PE8-Pad59)") (class "Default")
      (node (ref "U7") (pin "59") (pinfunction "PE8_59") (pintype "bidirectional+no_connect"))
    )
    (net (code "95") (name "unconnected-(U7A-PE9-Pad60)") (class "Default")
      (node (ref "U7") (pin "60") (pinfunction "PE9_60") (pintype "bidirectional+no_connect"))
    )
    (net (code "96") (name "unconnected-(U7A-PE10-Pad63)") (class "Default")
      (node (ref "U7") (pin "63") (pinfunction "PE10_63") (pintype "bidirectional+no_connect"))
    )
    (net (code "97") (name "unconnected-(U7A-PE11-Pad64)") (class "Default")
      (node (ref "U7") (pin "64") (pinfunction "PE11_64") (pintype "bidirectional+no_connect"))
    )
    (net (code "98") (name "unconnected-(U7A-PE12-Pad65)") (class "Default")
      (node (ref "U7") (pin "65") (pinfunction "PE12_65") (pintype "bidirectional+no_connect"))
    )
    (net (code "99") (name "unconnected-(U7A-PE13-Pad66)") (class "Default")
      (node (ref "U7") (pin "66") (pinfunction "PE13_66") (pintype "bidirectional+no_connect"))
    )
    (net (code "100") (name "unconnected-(U7A-PE14-Pad67)") (class "Default")
      (node (ref "U7") (pin "67") (pinfunction "PE14_67") (pintype "bidirectional+no_connect"))
    )
    (net (code "101") (name "unconnected-(U7A-PE15-Pad68)") (class "Default")
      (node (ref "U7") (pin "68") (pinfunction "PE15_68") (pintype "bidirectional+no_connect"))
    )
    (net (code "102") (name "unconnected-(U7A-PF0-Pad10)") (class "Default")
      (node (ref "U7") (pin "10") (pinfunction "PF0_10") (pintype "bidirectional+no_connect"))
    )
    (net (code "103") (name "unconnected-(U7A-PF4-Pad14)") (class "Default")
      (node (ref "U7") (pin "14") (pinfunction "PF4_14") (pintype "bidirectional+no_connect"))
    )
    (net (code "104") (name "unconnected-(U7A-PF5-Pad15)") (class "Default")
      (node (ref "U7") (pin "15") (pinfunction "PF5_15") (pintype "bidirectional+no_connect"))
    )
    (net (code "105") (name "unconnected-(U7A-PF6-Pad18)") (class "Default")
      (node (ref "U7") (pin "18") (pinfunction "PF6_18") (pintype "bidirectional+no_connect"))
    )
    (net (code "106") (name "unconnected-(U7A-PF7-Pad19)") (class "Default")
      (node (ref "U7") (pin "19") (pinfunction "PF7_19") (pintype "bidirectional+no_connect"))
    )
    (net (code "107") (name "unconnected-(U7A-PF8-Pad20)") (class "Default")
      (node (ref "U7") (pin "20") (pinfunction "PF8_20") (pintype "bidirectional+no_connect"))
    )
    (net (code "108") (name "unconnected-(U7A-PF9-Pad21)") (class "Default")
      (node (ref "U7") (pin "21") (pinfunction "PF9_21") (pintype "bidirectional+no_connect"))
    )
    (net (code "109") (name "unconnected-(U7A-PF10-Pad22)") (class "Default")
      (node (ref "U7") (pin "22") (pinfunction "PF10_22") (pintype "bidirectional+no_connect"))
    )
    (net (code "110") (name "unconnected-(U7A-PF11-Pad49)") (class "Default")
      (node (ref "U7") (pin "49") (pinfunction "PF11_49") (pintype "bidirectional+no_connect"))
    )
    (net (code "111") (name "unconnected-(U7A-PF12-Pad50)") (class "Default")
      (node (ref "U7") (pin "50") (pinfunction "PF12_50") (pintype "bidirectional+no_connect"))
    )
    (net (code "112") (name "unconnected-(U7A-PF13-Pad53)") (class "Default")
      (node (ref "U7") (pin "53") (pinfunction "PF13_53") (pintype "bidirectional+no_connect"))
    )
    (net (code "113") (name "unconnected-(U7A-PF14-Pad54)") (class "Default")
      (node (ref "U7") (pin "54") (pinfunction "PF14_54") (pintype "bidirectional+no_connect"))
    )
    (net (code "114") (name "unconnected-(U7A-PF15-Pad55)") (class "Default")
      (node (ref "U7") (pin "55") (pinfunction "PF15_55") (pintype "bidirectional+no_connect"))
    )
    (net (code "115") (name "unconnected-(U7B-PG0-Pad56)") (class "Default")
      (node (ref "U7") (pin "56") (pinfunction "PG0_56") (pintype "bidirectional+no_connect"))
    )
    (net (code "116") (name "unconnected-(U7B-PG1-Pad57)") (class "Default")
      (node (ref "U7") (pin "57") (pinfunction "PG1_57") (pintype "bidirectional+no_connect"))
    )
    (net (code "117") (name "unconnected-(U7B-PG2-Pad87)") (class "Default")
      (node (ref "U7") (pin "87") (pinfunction "PG2_87") (pintype "bidirectional+no_connect"))
    )
    (net (code "118") (name "unconnected-(U7B-PG3-Pad88)") (class "Default")
      (node (ref "U7") (pin "88") (pinfunction "PG3_88") (pintype "bidirectional+no_connect"))
    )
    (net (code "119") (name "unconnected-(U7B-PG4-Pad89)") (class "Default")
      (node (ref "U7") (pin "89") (pinfunction "PG4_89") (pintype "bidirectional+no_connect"))
    )
    (net (code "120") (name "unconnected-(U7B-PG5-Pad90)") (class "Default")
      (node (ref "U7") (pin "90") (pinfunction "PG5_90") (pintype "bidirectional+no_connect"))
    )
    (net (code "121") (name "unconnected-(U7B-PG8-Pad93)") (class "Default")
      (node (ref "U7") (pin "93") (pinfunction "PG8_93") (pintype "bidirectional+no_connect"))
    )
    (net (code "122") (name "unconnected-(U7B-PG9-Pad124)") (class "Default")
      (node (ref "U7") (pin "124") (pinfunction "PG9_124") (pintype "bidirectional+no_connect"))
    )
    (net (code "123") (name "unconnected-(U7B-PG10-Pad125)") (class "Default")
      (node (ref "U7") (pin "125") (pinfunction "PG10_125") (pintype "bidirectional+no_connect"))
    )
    (net (code "124") (name "unconnected-(U7B-PG11-Pad126)") (class "Default")
      (node (ref "U7") (pin "126") (pinfunction "PG11_126") (pintype "bidirectional+no_connect"))
    )
    (net (code "125") (name "unconnected-(U7B-PG12-Pad127)") (class "Default")
      (node (ref "U7") (pin "127") (pinfunction "PG12_127") (pintype "bidirectional+no_connect"))
    )
    (net (code "126") (name "unconnected-(U7B-PG13-Pad128)") (class "Default")
      (node (ref "U7") (pin "128") (pinfunction "PG13_128") (pintype "bidirectional+no_connect"))
    )
    (net (code "127") (name "unconnected-(U7B-PG14-Pad129)") (class "Default")
      (node (ref "U7") (pin "129") (pinfunction "PG14_129") (pintype "bidirectional+no_connect"))
    )
    (net (code "128") (name "unconnected-(U7B-PG15-Pad132)") (class "Default")
      (node (ref "U7") (pin "132") (pinfunction "PG15_132") (pintype "bidirectional+no_connect"))
    )
  )
)
